# Sheet1.net
KiCad netlist of a schematic drawn in Altium Designer
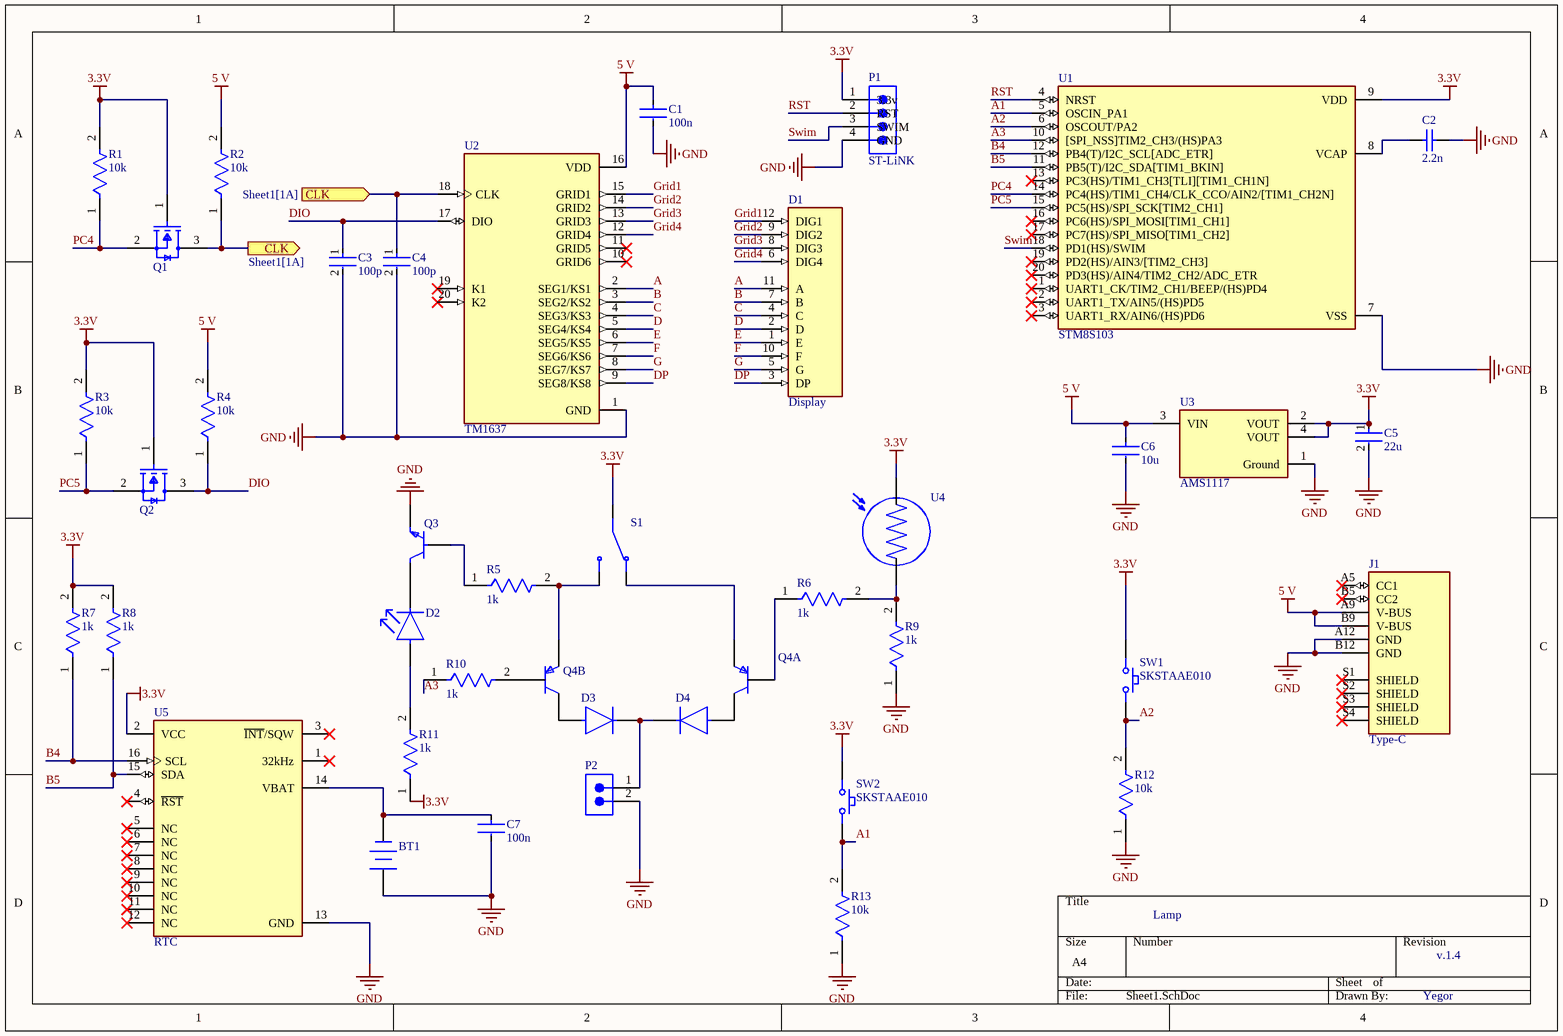
[diagram p0: Sheet1.SchDoc]

(export (version "E")
  (design (tool "Eeschema 10.0.6"))
  (components
    (comp (ref "BT1")
      (value "~")
      (footprint "PANA-CR-2032HFN")
      (description "Coin Cell Battery, 225 mAh, 0.2 mA, 3 V, -30 to 60 degC, Bulk")
      (fields (field (name "MANUFACTURER") "Panasonic"))
      (libsource (lib "Components - 25.08.25 - 13.52") (part "CMP-2000-05296-1"))
    )
    (comp (ref "C1")
      (value "100n")
      (footprint "FP-AC1206-0_85-IPC_C")
      (description "CAP CER 0.1UF 100V X7R 1206")
      (fields
        (field (name "OCTOPART") "https://octopart.com/ac1206kkx7r0bb104-yageo-75666120")
        (field (name "TOLERANCE") "0.1")
      )
      (libsource (lib "Components - 11.11.25 - 17.38") (part "CMP-03422-001145-1"))
    )
    (comp (ref "C2")
      (value "2.2n")
      (footprint "CAPC1206(3216)150_M")
      (description "CAP 2.2nF 100V ±1% 1206 (3216 Metric) Thickness 1.5mm SMD")
      (fields (field (name "TOLERANCE") "Â±1%"))
      (libsource (lib "Components - 11.11.25 - 17.47") (part "CMP-1037-02796-1"))
    )
    (comp (ref "C3")
      (value "100p")
      (footprint "FP-1206-L_3_2_0_2-W_1_6_0-IPC_B")
      (description "General Purpose Ceramic Capacitor, 1206, 100pF, 5%, NP0, 30ppm/°C, 100V")
      (fields (field (name "VOLTAGE") "63V") (field (name "TOLERANCE") "5%"))
      (libsource (lib "Components - 11.11.25 - 17.49") (part "CMP-04427-007664-1"))
    )
    (comp (ref "C4")
      (value "100p")
      (footprint "FP-1206-L_3_2_0_2-W_1_6_0-IPC_B")
      (description "General Purpose Ceramic Capacitor, 1206, 100pF, 5%, NP0, 30ppm/°C, 100V")
      (fields (field (name "VOLTAGE") "63V") (field (name "TOLERANCE") "5%"))
      (libsource (lib "Components - 11.11.25 - 17.49") (part "CMP-04427-007664-1"))
    )
    (comp (ref "C5")
      (value "22u")
      (footprint "FP-1206-L_3_2_0_2-W_1_6_0-MFG")
      (description "General Purpose Ceramic Capacitor, 1206, 22uF, 10%, X5R, 15%, 6.3V")
      (fields (field (name "TOLERANCE") "10%") (field (name "VOLTAGE") "6.3V"))
      (libsource (lib "Components - 11.11.25 - 17.43") (part "CMP-04427-006376-1"))
    )
    (comp (ref "C6")
      (value "10u")
      (footprint "FP-GCJ31C-0_4-MFG")
      (description "Cap Ceramic 10uF 35V X7T 10% SMD 1206 +125°C Embossed Plastic T/R")
      (libsource (lib "Components - 11.11.25 - 17.41") (part "CMP-06035-004889-1"))
    )
    (comp (ref "C7")
      (value "100n")
      (footprint "FP-AC1206-0_85-IPC_C")
      (description "CAP CER 0.1UF 100V X7R 1206")
      (fields
        (field (name "OCTOPART") "https://octopart.com/ac1206kkx7r0bb104-yageo-75666120")
        (field (name "TOLERANCE") "0.1")
      )
      (libsource (lib "Components - 11.11.25 - 17.38") (part "CMP-03422-001145-1"))
    )
    (comp (ref "D1")
      (value "Display")
      (footprint "LED_LDQ-M3604RI")
      (description "Display, Seven Segment, 9.2MM, Red")
      (fields (field (name "MF") "Lumex") (field (name "MP") "LDQ-M3604RI"))
      (libsource (lib "LDQ-M3604RI") (part "LDQ-M3604RI"))
    )
    (comp (ref "D2")
      (value "~")
      (footprint "FP-HLMP-1301-MFG")
      (description "LED RED DIFFUSED T-1 T/H")
      (fields
        (field (name "MANUFACTURER PART NUMBER") "HLMP-1301")
        (field (name "OCTOPART") "https://octopart.com/hlmp-1301-broadcom-71130345")
      )
      (libsource (lib "Components - 11.11.25 - 18.25") (part "CMP-18399-000007-1"))
    )
    (comp (ref "D3")
      (value "~")
      (footprint "FP-425AD-MFG")
      (description "S1JFL Rectifier Diode, 1 Phase, 1 Element, 1A, 600V V(RRM), Silicon")
      (libsource (lib "Components - 11.11.25 - 18.30") (part "CMP-00278-84331277-1"))
    )
    (comp (ref "D4")
      (value "~")
      (footprint "FP-425AD-MFG")
      (description "S1JFL Rectifier Diode, 1 Phase, 1 Element, 1A, 600V V(RRM), Silicon")
      (libsource (lib "Components - 11.11.25 - 18.30") (part "CMP-00278-84331277-1"))
    )
    (comp (ref "J1")
      (value "Type-C")
      (footprint "CUI_UJC-HP-3-SMT-TR")
      (fields (field (name "MP") "UJC-HP-3-SMT-TR"))
      (libsource (lib "UJC-HP-3-SMT-TR") (part "UJC-HP-3-SMT-TR"))
    )
    (comp (ref "P1")
      (value "ST-LiNK")
      (footprint "61300411021")
      (libsource (lib "Components - 25.08.25 - 11.48") (part "CMP-1502-01063-3"))
    )
    (comp (ref "P2")
      (value "~")
      (footprint "SMTC-TSW-102-26-XX-S")
      (description "0.025\" SQ Post Header, Through-hole, Vertical, -55 to 125 degC, 2.54 mm Pitch, 2-Pin, Male, RoHS")
      (fields (field (name "PARTNUMBER") "TSW-102-26-G-S") (field (name "MANUFACTURER") "Samtec"))
      (libsource (lib "Components - 11.11.25 - 18.36") (part "CMP-1024-00327-1"))
    )
    (comp (ref "Q1")
      (value "~")
      (footprint "FP-318-08-MFG")
      (description "MOSFET N-CH 50V 220MA SOT-23")
      (libsource (lib "Components - 11.11.25 - 17.32") (part "CMP-07173-000101-1"))
    )
    (comp (ref "Q2")
      (value "~")
      (footprint "FP-318-08-MFG")
      (description "MOSFET N-CH 50V 220MA SOT-23")
      (libsource (lib "Components - 11.11.25 - 17.32") (part "CMP-07173-000101-1"))
    )
    (comp (ref "Q3")
      (value "~")
      (footprint "PLZZ0004CA-A_MFG")
      (description "Trans GP BJT NPN 50V 1A 4-Pin(3+Tab) UPAK T/R")
      (libsource (lib "Components - 25.08.25 - 21.28") (part "CMP-00572-18697870-1"))
    )
    (comp (ref "Q4")
      (value "~")
      (footprint "SOT95P280X145-6_P6_064_N")
      (description "Transistor, Bjt, Pair, Pnp, 11V V(Br)Ceo, 14Ma I(C), So")
      (libsource (lib "Components - 25.08.25 - 12.53") (part "CMP-00572-88253858-3"))
    )
    (comp (ref "R1")
      (value "10k")
      (footprint "FP-CRCW1206-e3-IPC_B")
      (description "Res MC AT Professional Thin Film 1206 10kΩ 0.5% 0.4W ±25ppm/°C Molded Paper T/R")
      (fields (field (name "TOLERANCE") "0.5%"))
      (libsource (lib "Components - 12.11.25 - 15.52") (part "CMP-02407-011266-1"))
    )
    (comp (ref "R2")
      (value "10k")
      (footprint "FP-CRCW1206-e3-IPC_B")
      (description "Res MC AT Professional Thin Film 1206 10kΩ 0.5% 0.4W ±25ppm/°C Molded Paper T/R")
      (fields (field (name "TOLERANCE") "0.5%"))
      (libsource (lib "Components - 12.11.25 - 15.52") (part "CMP-02407-011266-1"))
    )
    (comp (ref "R3")
      (value "10k")
      (footprint "FP-CRCW1206-e3-IPC_B")
      (description "Res MC AT Professional Thin Film 1206 10kΩ 0.5% 0.4W ±25ppm/°C Molded Paper T/R")
      (fields (field (name "TOLERANCE") "0.5%"))
      (libsource (lib "Components - 12.11.25 - 15.52") (part "CMP-02407-011266-1"))
    )
    (comp (ref "R4")
      (value "10k")
      (footprint "FP-CRCW1206-e3-IPC_B")
      (description "Res MC AT Professional Thin Film 1206 10kΩ 0.5% 0.4W ±25ppm/°C Molded Paper T/R")
      (fields (field (name "TOLERANCE") "0.5%"))
      (libsource (lib "Components - 12.11.25 - 15.52") (part "CMP-02407-011266-1"))
    )
    (comp (ref "R5")
      (value "1k")
      (footprint "FP-RP732B-IPC_C")
      (description "Res Thin Film 1206 1.0KΩ 0.1% 0.25W 15ppm/°C Molded SMD")
      (fields
        (field (name "OCTOPART") "https://octopart.com/rp73d2b1k0btg-te+connectivity-42012461")
        (field (name "MANUFACTURER") "TE Connectivity")
      )
      (libsource (lib "Components - 12.11.25 - 16.01") (part "CMP-03211-008960-1"))
    )
    (comp (ref "R6")
      (value "1k")
      (footprint "FP-RP732B-IPC_C")
      (description "Res Thin Film 1206 1.0KΩ 0.1% 0.25W 15ppm/°C Molded SMD")
      (fields
        (field (name "OCTOPART") "https://octopart.com/rp73d2b1k0btg-te+connectivity-42012461")
        (field (name "MANUFACTURER") "TE Connectivity")
      )
      (libsource (lib "Components - 12.11.25 - 16.01") (part "CMP-03211-008960-1"))
    )
    (comp (ref "R7")
      (value "1k")
      (footprint "FP-RP732B-IPC_C")
      (description "Res Thin Film 1206 1.0KΩ 0.1% 0.25W 15ppm/°C Molded SMD")
      (fields
        (field (name "OCTOPART") "https://octopart.com/rp73d2b1k0btg-te+connectivity-42012461")
        (field (name "MANUFACTURER") "TE Connectivity")
      )
      (libsource (lib "Components - 12.11.25 - 16.01") (part "CMP-03211-008960-1"))
    )
    (comp (ref "R8")
      (value "1k")
      (footprint "FP-RP732B-IPC_C")
      (description "Res Thin Film 1206 1.0KΩ 0.1% 0.25W 15ppm/°C Molded SMD")
      (fields
        (field (name "OCTOPART") "https://octopart.com/rp73d2b1k0btg-te+connectivity-42012461")
        (field (name "MANUFACTURER") "TE Connectivity")
      )
      (libsource (lib "Components - 12.11.25 - 16.01") (part "CMP-03211-008960-1"))
    )
    (comp (ref "R9")
      (value "1k")
      (footprint "FP-RP732B-IPC_C")
      (description "Res Thin Film 1206 1.0KΩ 0.1% 0.25W 15ppm/°C Molded SMD")
      (fields
        (field (name "OCTOPART") "https://octopart.com/rp73d2b1k0btg-te+connectivity-42012461")
        (field (name "MANUFACTURER") "TE Connectivity")
      )
      (libsource (lib "Components - 12.11.25 - 16.01") (part "CMP-03211-008960-1"))
    )
    (comp (ref "R10")
      (value "1k")
      (footprint "FP-RP732B-IPC_C")
      (description "Res Thin Film 1206 1.0KΩ 0.1% 0.25W 15ppm/°C Molded SMD")
      (fields
        (field (name "OCTOPART") "https://octopart.com/rp73d2b1k0btg-te+connectivity-42012461")
        (field (name "MANUFACTURER") "TE Connectivity")
      )
      (libsource (lib "Components - 12.11.25 - 16.01") (part "CMP-03211-008960-1"))
    )
    (comp (ref "R11")
      (value "1k")
      (footprint "FP-RP732B-IPC_C")
      (description "Res Thin Film 1206 1.0KΩ 0.1% 0.25W 15ppm/°C Molded SMD")
      (fields
        (field (name "OCTOPART") "https://octopart.com/rp73d2b1k0btg-te+connectivity-42012461")
        (field (name "MANUFACTURER") "TE Connectivity")
      )
      (libsource (lib "Components - 12.11.25 - 16.01") (part "CMP-03211-008960-1"))
    )
    (comp (ref "R12")
      (value "10k")
      (footprint "FP-CRCW1206-e3-IPC_B")
      (description "Res MC AT Professional Thin Film 1206 10kΩ 0.5% 0.4W ±25ppm/°C Molded Paper T/R")
      (fields (field (name "TOLERANCE") "0.5%"))
      (libsource (lib "Components - 12.11.25 - 15.52") (part "CMP-02407-011266-1"))
    )
    (comp (ref "R13")
      (value "10k")
      (footprint "FP-CRCW1206-e3-IPC_B")
      (description "Res MC AT Professional Thin Film 1206 10kΩ 0.5% 0.4W ±25ppm/°C Molded Paper T/R")
      (fields (field (name "TOLERANCE") "0.5%"))
      (libsource (lib "Components - 12.11.25 - 15.52") (part "CMP-02407-011266-1"))
    )
    (comp (ref "S1")
      (value "~")
      (footprint "SW_MINI-SPDT-SW")
      (fields (field (name "MP") "MINI-SPDT-SW"))
      (libsource (lib "MINI-SPDT-SW") (part "MINI-SPDT-SW"))
    )
    (comp (ref "SW1")
      (value "SKSTAAE010")
      (footprint "FP-SKSTAAE010-MFG")
      (description "Tactile Switches Quiet 0.9mm Middle Stroke, 4N,500KCycle")
      (libsource (lib "Components - 11.11.25 - 17.51") (part "CMP-24311-000002-1"))
    )
    (comp (ref "SW2")
      (value "SKSTAAE010")
      (footprint "FP-SKSTAAE010-MFG")
      (description "Tactile Switches Quiet 0.9mm Middle Stroke, 4N,500KCycle")
      (libsource (lib "Components - 11.11.25 - 17.51") (part "CMP-24311-000002-1"))
    )
    (comp (ref "U1")
      (value "STM8S103")
      (footprint "SOP65P640X120-20N")
      (description "STM8 series Microcontroller IC 8-Bit 16MHz 8KB (8K x 8) FLASH 20-TSSOP")
      (fields (field (name "MF") "STMicroelectronics") (field (name "MP") "STM8S103F3P6"))
      (libsource (lib "STM8S103F3P6") (part "STM8S103F3P6"))
    )
    (comp (ref "U2")
      (value "TM1637")
      (footprint "SOIC127P1035X255-20N")
      (description "LED Drive Control Special Circuit")
      (fields (field (name "MF") "Titan Micro Electronics") (field (name "MP") "TM1637_SOP20"))
      (libsource (lib "TM1637_SOP20") (part "TM1637_SOP20"))
    )
    (comp (ref "U3")
      (value "AMS1117")
      (footprint "FP-AMS1117-IPC_A")
      (description "LDO Voltage Regulators 1A, 3.3V")
      (fields
        (field (name "MANUFACTURER PART NUMBER") "AMS1117-3.3")
        (field (name "OCTOPART") "https://octopart.com/ams1117-3.3-advanced+monolithic+systems-25899300")
      )
      (libsource (lib "Components - 25.08.25 - 12.03") (part "CMP-209535-000001-1"))
    )
    (comp (ref "U4")
      (value "~")
      (footprint "XDCR_PDV-P8003")
      (description "CdS Cells 520nm 16 ~ 33kOhms @ 10 lux")
      (fields (field (name "MF") "Advanced Photonix") (field (name "MP") "PDV-P8003"))
      (libsource (lib "PDV-P8003") (part "PDV-P8003"))
    )
    (comp (ref "U5")
      (value "RTC")
      (footprint "FP-W16-H2-MFG")
      (description "IC RTC CLK/CALENDAR I2C 16-SOIC")
      (libsource (lib "Components - 25.08.25 - 13.49") (part "CMP-0254-00375-2"))
    )
  )
  (nets
    (net (code "1") (name "/A") (class "Default")
      (node (ref "D1") (pin "11") (pinfunction "A_11") (pintype "input"))
      (node (ref "U2") (pin "2") (pinfunction "SEG1/KS1_2") (pintype "output"))
    )
    (net (code "2") (name "/A1") (class "Default")
      (node (ref "R13") (pin "2") (pinfunction "2_2") (pintype "passive"))
      (node (ref "SW2") (pin "2") (pinfunction "2_2") (pintype "passive"))
      (node (ref "U1") (pin "5") (pinfunction "OSCIN_PA1_5") (pintype "bidirectional"))
    )
    (net (code "3") (name "/A2") (class "Default")
      (node (ref "R12") (pin "2") (pinfunction "2_2") (pintype "passive"))
      (node (ref "SW1") (pin "2") (pinfunction "2_2") (pintype "passive"))
      (node (ref "U1") (pin "6") (pinfunction "OSCOUT/PA2_6") (pintype "bidirectional"))
    )
    (net (code "4") (name "/A3") (class "Default")
      (node (ref "R10") (pin "1") (pinfunction "1_1") (pintype "passive"))
      (node (ref "U1") (pin "10") (pinfunction "[SPI_NSS]TIM2_CH3/(HS)PA3_10") (pintype "bidirectional"))
    )
    (net (code "5") (name "/B") (class "Default")
      (node (ref "D1") (pin "7") (pinfunction "B_7") (pintype "input"))
      (node (ref "U2") (pin "3") (pinfunction "SEG2/KS2_3") (pintype "output"))
    )
    (net (code "6") (name "/B4") (class "Default")
      (node (ref "R7") (pin "1") (pinfunction "1_1") (pintype "passive"))
      (node (ref "U1") (pin "12") (pinfunction "PB4(T)/I2C_SCL[ADC_ETR]_12") (pintype "bidirectional"))
      (node (ref "U5") (pin "16") (pinfunction "SCL_16") (pintype "input"))
    )
    (net (code "7") (name "/B5") (class "Default")
      (node (ref "R8") (pin "1") (pinfunction "1_1") (pintype "passive"))
      (node (ref "U1") (pin "11") (pinfunction "PB5(T)/I2C_SDA[TIM1_BKIN]_11") (pintype "bidirectional"))
      (node (ref "U5") (pin "15") (pinfunction "SDA_15") (pintype "bidirectional"))
    )
    (net (code "8") (name "/C") (class "Default")
      (node (ref "D1") (pin "4") (pinfunction "C_4") (pintype "input"))
      (node (ref "U2") (pin "4") (pinfunction "SEG3/KS3_4") (pintype "output"))
    )
    (net (code "9") (name "/CLK") (class "Default")
      (node (ref "C4") (pin "1") (pinfunction "1_1") (pintype "passive"))
      (node (ref "Q1") (pin "3") (pinfunction "D_3") (pintype "passive"))
      (node (ref "R2") (pin "1") (pinfunction "1_1") (pintype "passive"))
      (node (ref "U2") (pin "18") (pinfunction "CLK_18") (pintype "input"))
    )
    (net (code "10") (name "/D") (class "Default")
      (node (ref "D1") (pin "2") (pinfunction "D_2") (pintype "input"))
      (node (ref "U2") (pin "5") (pinfunction "SEG4/KS4_5") (pintype "output"))
    )
    (net (code "11") (name "/DIO") (class "Default")
      (node (ref "C3") (pin "1") (pinfunction "1_1") (pintype "passive"))
      (node (ref "Q2") (pin "3") (pinfunction "D_3") (pintype "passive"))
      (node (ref "R4") (pin "1") (pinfunction "1_1") (pintype "passive"))
      (node (ref "U2") (pin "17") (pinfunction "DIO_17") (pintype "bidirectional"))
    )
    (net (code "12") (name "/DP") (class "Default")
      (node (ref "D1") (pin "3") (pinfunction "DP_3") (pintype "input"))
      (node (ref "U2") (pin "9") (pinfunction "SEG8/KS8_9") (pintype "output"))
    )
    (net (code "13") (name "/E") (class "Default")
      (node (ref "D1") (pin "1") (pinfunction "E_1") (pintype "input"))
      (node (ref "U2") (pin "6") (pinfunction "SEG5/KS5_6") (pintype "output"))
    )
    (net (code "14") (name "/F") (class "Default")
      (node (ref "D1") (pin "10") (pinfunction "F_10") (pintype "input"))
      (node (ref "U2") (pin "7") (pinfunction "SEG6/KS6_7") (pintype "output"))
    )
    (net (code "15") (name "/G") (class "Default")
      (node (ref "D1") (pin "5") (pinfunction "G_5") (pintype "input"))
      (node (ref "U2") (pin "8") (pinfunction "SEG7/KS7_8") (pintype "output"))
    )
    (net (code "16") (name "/Grid1") (class "Default")
      (node (ref "D1") (pin "12") (pinfunction "DIG1_12") (pintype "input"))
      (node (ref "U2") (pin "15") (pinfunction "GRID1_15") (pintype "output"))
    )
    (net (code "17") (name "/Grid2") (class "Default")
      (node (ref "D1") (pin "9") (pinfunction "DIG2_9") (pintype "input"))
      (node (ref "U2") (pin "14") (pinfunction "GRID2_14") (pintype "output"))
    )
    (net (code "18") (name "/Grid3") (class "Default")
      (node (ref "D1") (pin "8") (pinfunction "DIG3_8") (pintype "input"))
      (node (ref "U2") (pin "13") (pinfunction "GRID3_13") (pintype "output"))
    )
    (net (code "19") (name "/Grid4") (class "Default")
      (node (ref "D1") (pin "6") (pinfunction "DIG4_6") (pintype "input"))
      (node (ref "U2") (pin "12") (pinfunction "GRID4_12") (pintype "output"))
    )
    (net (code "20") (name "/PC4") (class "Default")
      (node (ref "Q1") (pin "2") (pinfunction "S_2") (pintype "passive"))
      (node (ref "R1") (pin "1") (pinfunction "1_1") (pintype "passive"))
      (node (ref "U1") (pin "14") (pinfunction "PC4(HS)/TIM1_CH4/CLK_CCO/AIN2/[TIM1_CH2N]_14") (pintype "bidirectional"))
    )
    (net (code "21") (name "/PC5") (class "Default")
      (node (ref "Q2") (pin "2") (pinfunction "S_2") (pintype "passive"))
      (node (ref "R3") (pin "1") (pinfunction "1_1") (pintype "passive"))
      (node (ref "U1") (pin "15") (pinfunction "PC5(HS)/SPI_SCK[TIM2_CH1]_15") (pintype "bidirectional"))
    )
    (net (code "22") (name "/RST") (class "Default")
      (node (ref "P1") (pin "2") (pinfunction "RST_2") (pintype "passive"))
      (node (ref "U1") (pin "4") (pinfunction "NRST_4") (pintype "bidirectional"))
    )
    (net (code "23") (name "/Swim") (class "Default")
      (node (ref "P1") (pin "3") (pinfunction "SWIM_3") (pintype "passive"))
      (node (ref "U1") (pin "18") (pinfunction "PD1(HS)/SWIM_18") (pintype "bidirectional"))
    )
    (net (code "24") (name "3.3V") (class "Default")
      (node (ref "C5") (pin "1") (pinfunction "1_1") (pintype "passive"))
      (node (ref "P1") (pin "1") (pinfunction "3.3v_1") (pintype "passive"))
      (node (ref "Q1") (pin "1") (pinfunction "G_1") (pintype "passive"))
      (node (ref "Q2") (pin "1") (pinfunction "G_1") (pintype "passive"))
      (node (ref "R1") (pin "2") (pinfunction "2_2") (pintype "passive"))
      (node (ref "R11") (pin "1") (pinfunction "1_1") (pintype "passive"))
      (node (ref "R3") (pin "2") (pinfunction "2_2") (pintype "passive"))
      (node (ref "R7") (pin "2") (pinfunction "2_2") (pintype "passive"))
      (node (ref "R8") (pin "2") (pinfunction "2_2") (pintype "passive"))
      (node (ref "S1") (pin "2") (pinfunction "2_2") (pintype "passive"))
      (node (ref "SW1") (pin "1") (pinfunction "1_1") (pintype "passive"))
      (node (ref "SW2") (pin "1") (pinfunction "1_1") (pintype "passive"))
      (node (ref "U1") (pin "9") (pinfunction "VDD_9") (pintype "power_in"))
      (node (ref "U3") (pin "2") (pinfunction "VOUT_2") (pintype "passive"))
      (node (ref "U3") (pin "4") (pinfunction "VOUT_4") (pintype "passive"))
      (node (ref "U4") (pin "2") (pinfunction "2_2") (pintype "passive"))
      (node (ref "U5") (pin "2") (pinfunction "VCC_2") (pintype "power_in"))
    )
    (net (code "25") (name "5 V") (class "Default")
      (node (ref "C1") (pin "1") (pinfunction "1_1") (pintype "passive"))
      (node (ref "C6") (pin "1") (pinfunction "1_1") (pintype "passive"))
      (node (ref "J1") (pin "A9") (pinfunction "V-BUS_A9") (pintype "power_in"))
      (node (ref "J1") (pin "B9") (pinfunction "V-BUS_B9") (pintype "power_in"))
      (node (ref "R2") (pin "2") (pinfunction "2_2") (pintype "passive"))
      (node (ref "R4") (pin "2") (pinfunction "2_2") (pintype "passive"))
      (node (ref "U2") (pin "16") (pinfunction "VDD_16") (pintype "power_in"))
      (node (ref "U3") (pin "3") (pinfunction "VIN_3") (pintype "power_in"))
    )
    (net (code "26") (name "GND") (class "Default")
      (node (ref "BT1") (pin "1") (pinfunction "+_1") (pintype "passive"))
      (node (ref "C1") (pin "2") (pinfunction "2_2") (pintype "passive"))
      (node (ref "C2") (pin "2") (pinfunction "2_2") (pintype "passive"))
      (node (ref "C3") (pin "2") (pinfunction "2_2") (pintype "passive"))
      (node (ref "C4") (pin "2") (pinfunction "2_2") (pintype "passive"))
      (node (ref "C5") (pin "2") (pinfunction "2_2") (pintype "passive"))
      (node (ref "C6") (pin "2") (pinfunction "2_2") (pintype "passive"))
      (node (ref "C7") (pin "2") (pinfunction "2_2") (pintype "passive"))
      (node (ref "J1") (pin "A12") (pinfunction "GND_A12") (pintype "power_in"))
      (node (ref "J1") (pin "B12") (pinfunction "GND_B12") (pintype "power_in"))
      (node (ref "P1") (pin "4") (pinfunction "GND_4") (pintype "passive"))
      (node (ref "P2") (pin "2") (pinfunction "2_2") (pintype "passive"))
      (node (ref "Q3") (pin "3") (pinfunction "EMITTER_3") (pintype "passive"))
      (node (ref "R12") (pin "1") (pinfunction "1_1") (pintype "passive"))
      (node (ref "R13") (pin "1") (pinfunction "1_1") (pintype "passive"))
      (node (ref "R9") (pin "1") (pinfunction "1_1") (pintype "passive"))
      (node (ref "U1") (pin "7") (pinfunction "VSS_7") (pintype "power_in"))
      (node (ref "U2") (pin "1") (pinfunction "GND_1") (pintype "power_in"))
      (node (ref "U3") (pin "1") (pinfunction "Ground_1") (pintype "power_in"))
      (node (ref "U5") (pin "13") (pinfunction "GND_13") (pintype "power_in"))
    )
    (net (code "27") (name "Net-(BT1--)") (class "Default")
      (node (ref "BT1") (pin "2") (pinfunction "-_2") (pintype "passive"))
      (node (ref "C7") (pin "1") (pinfunction "1_1") (pintype "passive"))
      (node (ref "U5") (pin "14") (pinfunction "VBAT_14") (pintype "power_in"))
    )
    (net (code "28") (name "Net-(D2-A)") (class "Default")
      (node (ref "D2") (pin "2") (pinfunction "A_2") (pintype "passive"))
      (node (ref "R11") (pin "2") (pinfunction "2_2") (pintype "passive"))
    )
    (net (code "29") (name "Net-(D2-C)") (class "Default")
      (node (ref "D2") (pin "1") (pinfunction "C_1") (pintype "passive"))
      (node (ref "Q3") (pin "2") (pinfunction "COLLECTOR_2") (pintype "passive"))
    )
    (net (code "30") (name "Net-(D3-A)") (class "Default")
      (node (ref "D3") (pin "2") (pinfunction "A_2") (pintype "passive"))
      (node (ref "Q4") (pin "3") (pinfunction "2_COLLECTOR_3") (pintype "passive"))
    )
    (net (code "31") (name "Net-(D3-C)") (class "Default")
      (node (ref "D3") (pin "1") (pinfunction "C_1") (pintype "passive"))
      (node (ref "D4") (pin "1") (pinfunction "C_1") (pintype "passive"))
      (node (ref "P2") (pin "1") (pinfunction "1_1") (pintype "passive"))
    )
    (net (code "32") (name "Net-(D4-A)") (class "Default")
      (node (ref "D4") (pin "2") (pinfunction "A_2") (pintype "passive"))
      (node (ref "Q4") (pin "6") (pinfunction "1_COLLECTOR_6") (pintype "passive"))
    )
    (net (code "33") (name "Net-(Q3-BASE)") (class "Default")
      (node (ref "Q3") (pin "1") (pinfunction "BASE_1") (pintype "passive"))
      (node (ref "R5") (pin "1") (pinfunction "1_1") (pintype "passive"))
    )
    (net (code "34") (name "Net-(Q4A-1_BASE)") (class "Default")
      (node (ref "Q4") (pin "1") (pinfunction "1_BASE_1") (pintype "passive"))
      (node (ref "R6") (pin "1") (pinfunction "1_1") (pintype "passive"))
    )
    (net (code "35") (name "Net-(Q4A-1_EMITTER)") (class "Default")
      (node (ref "Q4") (pin "2") (pinfunction "1_EMITTER_2") (pintype "passive"))
      (node (ref "S1") (pin "1") (pinfunction "1_1") (pintype "passive"))
    )
    (net (code "36") (name "Net-(Q4B-2_BASE)") (class "Default")
      (node (ref "Q4") (pin "4") (pinfunction "2_BASE_4") (pintype "passive"))
      (node (ref "R10") (pin "2") (pinfunction "2_2") (pintype "passive"))
    )
    (net (code "37") (name "Net-(Q4B-2_EMITTER)") (class "Default")
      (node (ref "Q4") (pin "5") (pinfunction "2_EMITTER_5") (pintype "passive"))
      (node (ref "R5") (pin "2") (pinfunction "2_2") (pintype "passive"))
      (node (ref "S1") (pin "3") (pinfunction "3_3") (pintype "passive"))
    )
    (net (code "38") (name "Net-(R6-Pad2)") (class "Default")
      (node (ref "R6") (pin "2") (pinfunction "2_2") (pintype "passive"))
      (node (ref "R9") (pin "2") (pinfunction "2_2") (pintype "passive"))
      (node (ref "U4") (pin "1") (pinfunction "1_1") (pintype "passive"))
    )
    (net (code "39") (name "Net-(U1-VCAP)") (class "Default")
      (node (ref "C2") (pin "1") (pinfunction "1_1") (pintype "passive"))
      (node (ref "U1") (pin "8") (pinfunction "VCAP_8") (pintype "passive"))
    )
    (net (code "40") (name "unconnected-(J1-CC1-PadA5)") (class "Default")
      (node (ref "J1") (pin "A5") (pinfunction "CC1_A5") (pintype "bidirectional+no_connect"))
    )
    (net (code "41") (name "unconnected-(J1-CC2-PadB5)") (class "Default")
      (node (ref "J1") (pin "B5") (pinfunction "CC2_B5") (pintype "bidirectional+no_connect"))
    )
    (net (code "42") (name "unconnected-(J1-SHIELD-PadS1)") (class "Default")
      (node (ref "J1") (pin "S1") (pinfunction "SHIELD_S1") (pintype "passive+no_connect"))
    )
    (net (code "43") (name "unconnected-(J1-SHIELD-PadS2)") (class "Default")
      (node (ref "J1") (pin "S2") (pinfunction "SHIELD_S2") (pintype "passive+no_connect"))
    )
    (net (code "44") (name "unconnected-(J1-SHIELD-PadS3)") (class "Default")
      (node (ref "J1") (pin "S3") (pinfunction "SHIELD_S3") (pintype "passive+no_connect"))
    )
    (net (code "45") (name "unconnected-(J1-SHIELD-PadS4)") (class "Default")
      (node (ref "J1") (pin "S4") (pinfunction "SHIELD_S4") (pintype "passive+no_connect"))
    )
    (net (code "46") (name "unconnected-(U1-PC3(HS){slash}TIM1_CH3[TLI][TIM1_CH1N]-Pad13)") (class "Default")
      (node (ref "U1") (pin "13") (pinfunction "PC3(HS)/TIM1_CH3[TLI][TIM1_CH1N]_13") (pintype "bidirectional+no_connect"))
    )
    (net (code "47") (name "unconnected-(U1-PC6(HS){slash}SPI_MOSI[TIM1_CH1]-Pad16)") (class "Default")
      (node (ref "U1") (pin "16") (pinfunction "PC6(HS)/SPI_MOSI[TIM1_CH1]_16") (pintype "bidirectional+no_connect"))
    )
    (net (code "48") (name "unconnected-(U1-PC7(HS){slash}SPI_MISO[TIM1_CH2]-Pad17)") (class "Default")
      (node (ref "U1") (pin "17") (pinfunction "PC7(HS)/SPI_MISO[TIM1_CH2]_17") (pintype "bidirectional+no_connect"))
    )
    (net (code "49") (name "unconnected-(U1-PD2(HS){slash}AIN3{slash}[TIM2_CH3]-Pad19)") (class "Default")
      (node (ref "U1") (pin "19") (pinfunction "PD2(HS)/AIN3/[TIM2_CH3]_19") (pintype "bidirectional+no_connect"))
    )
    (net (code "50") (name "unconnected-(U1-PD3(HS){slash}AIN4{slash}TIM2_CH2{slash}ADC_ETR-Pad20)") (class "Default")
      (node (ref "U1") (pin "20") (pinfunction "PD3(HS)/AIN4/TIM2_CH2/ADC_ETR_20") (pintype "bidirectional+no_connect"))
    )
    (net (code "51") (name "unconnected-(U1-UART1_CK{slash}TIM2_CH1{slash}BEEP{slash}(HS)PD4-Pad1)") (class "Default")
      (node (ref "U1") (pin "1") (pinfunction "UART1_CK/TIM2_CH1/BEEP/(HS)PD4_1") (pintype "bidirectional+no_connect"))
    )
    (net (code "52") (name "unconnected-(U1-UART1_RX{slash}AIN6{slash}(HS)PD6-Pad3)") (class "Default")
      (node (ref "U1") (pin "3") (pinfunction "UART1_RX/AIN6/(HS)PD6_3") (pintype "bidirectional+no_connect"))
    )
    (net (code "53") (name "unconnected-(U1-UART1_TX{slash}AIN5{slash}(HS)PD5-Pad2)") (class "Default")
      (node (ref "U1") (pin "2") (pinfunction "UART1_TX/AIN5/(HS)PD5_2") (pintype "bidirectional+no_connect"))
    )
    (net (code "54") (name "unconnected-(U2-GRID5-Pad11)") (class "Default")
      (node (ref "U2") (pin "11") (pinfunction "GRID5_11") (pintype "output+no_connect"))
    )
    (net (code "55") (name "unconnected-(U2-GRID6-Pad10)") (class "Default")
      (node (ref "U2") (pin "10") (pinfunction "GRID6_10") (pintype "output+no_connect"))
    )
    (net (code "56") (name "unconnected-(U2-K1-Pad19)") (class "Default")
      (node (ref "U2") (pin "19") (pinfunction "K1_19") (pintype "input+no_connect"))
    )
    (net (code "57") (name "unconnected-(U2-K2-Pad20)") (class "Default")
      (node (ref "U2") (pin "20") (pinfunction "K2_20") (pintype "input+no_connect"))
    )
    (net (code "58") (name "unconnected-(U5-32kHz-Pad1)") (class "Default")
      (node (ref "U5") (pin "1") (pinfunction "32kHz_1") (pintype "open_collector+no_connect"))
    )
    (net (code "59") (name "unconnected-(U5-NC-Pad5)") (class "Default")
      (node (ref "U5") (pin "5") (pinfunction "NC_5") (pintype "passive+no_connect"))
    )
    (net (code "60") (name "unconnected-(U5-NC-Pad6)") (class "Default")
      (node (ref "U5") (pin "6") (pinfunction "NC_6") (pintype "passive+no_connect"))
    )
    (net (code "61") (name "unconnected-(U5-NC-Pad7)") (class "Default")
      (node (ref "U5") (pin "7") (pinfunction "NC_7") (pintype "passive+no_connect"))
    )
    (net (code "62") (name "unconnected-(U5-NC-Pad8)") (class "Default")
      (node (ref "U5") (pin "8") (pinfunction "NC_8") (pintype "passive+no_connect"))
    )
    (net (code "63") (name "unconnected-(U5-NC-Pad9)") (class "Default")
      (node (ref "U5") (pin "9") (pinfunction "NC_9") (pintype "passive+no_connect"))
    )
    (net (code "64") (name "unconnected-(U5-NC-Pad10)") (class "Default")
      (node (ref "U5") (pin "10") (pinfunction "NC_10") (pintype "passive+no_connect"))
    )
    (net (code "65") (name "unconnected-(U5-NC-Pad11)") (class "Default")
      (node (ref "U5") (pin "11") (pinfunction "NC_11") (pintype "passive+no_connect"))
    )
    (net (code "66") (name "unconnected-(U5-NC-Pad12)") (class "Default")
      (node (ref "U5") (pin "12") (pinfunction "NC_12") (pintype "passive+no_connect"))
    )
    (net (code "67") (name "unconnected-(U5-~{INT}{slash}SQW-Pad3)") (class "Default")
      (node (ref "U5") (pin "3") (pinfunction "~{INT}/SQW_3") (pintype "open_collector+no_connect"))
    )
    (net (code "68") (name "unconnected-(U5-~{RST}-Pad4)") (class "Default")
      (node (ref "U5") (pin "4") (pinfunction "~{RST}_4") (pintype "bidirectional+no_connect"))
    )
  )
)
